# PWR.net
KiCad netlist of a schematic drawn in Altium Designer
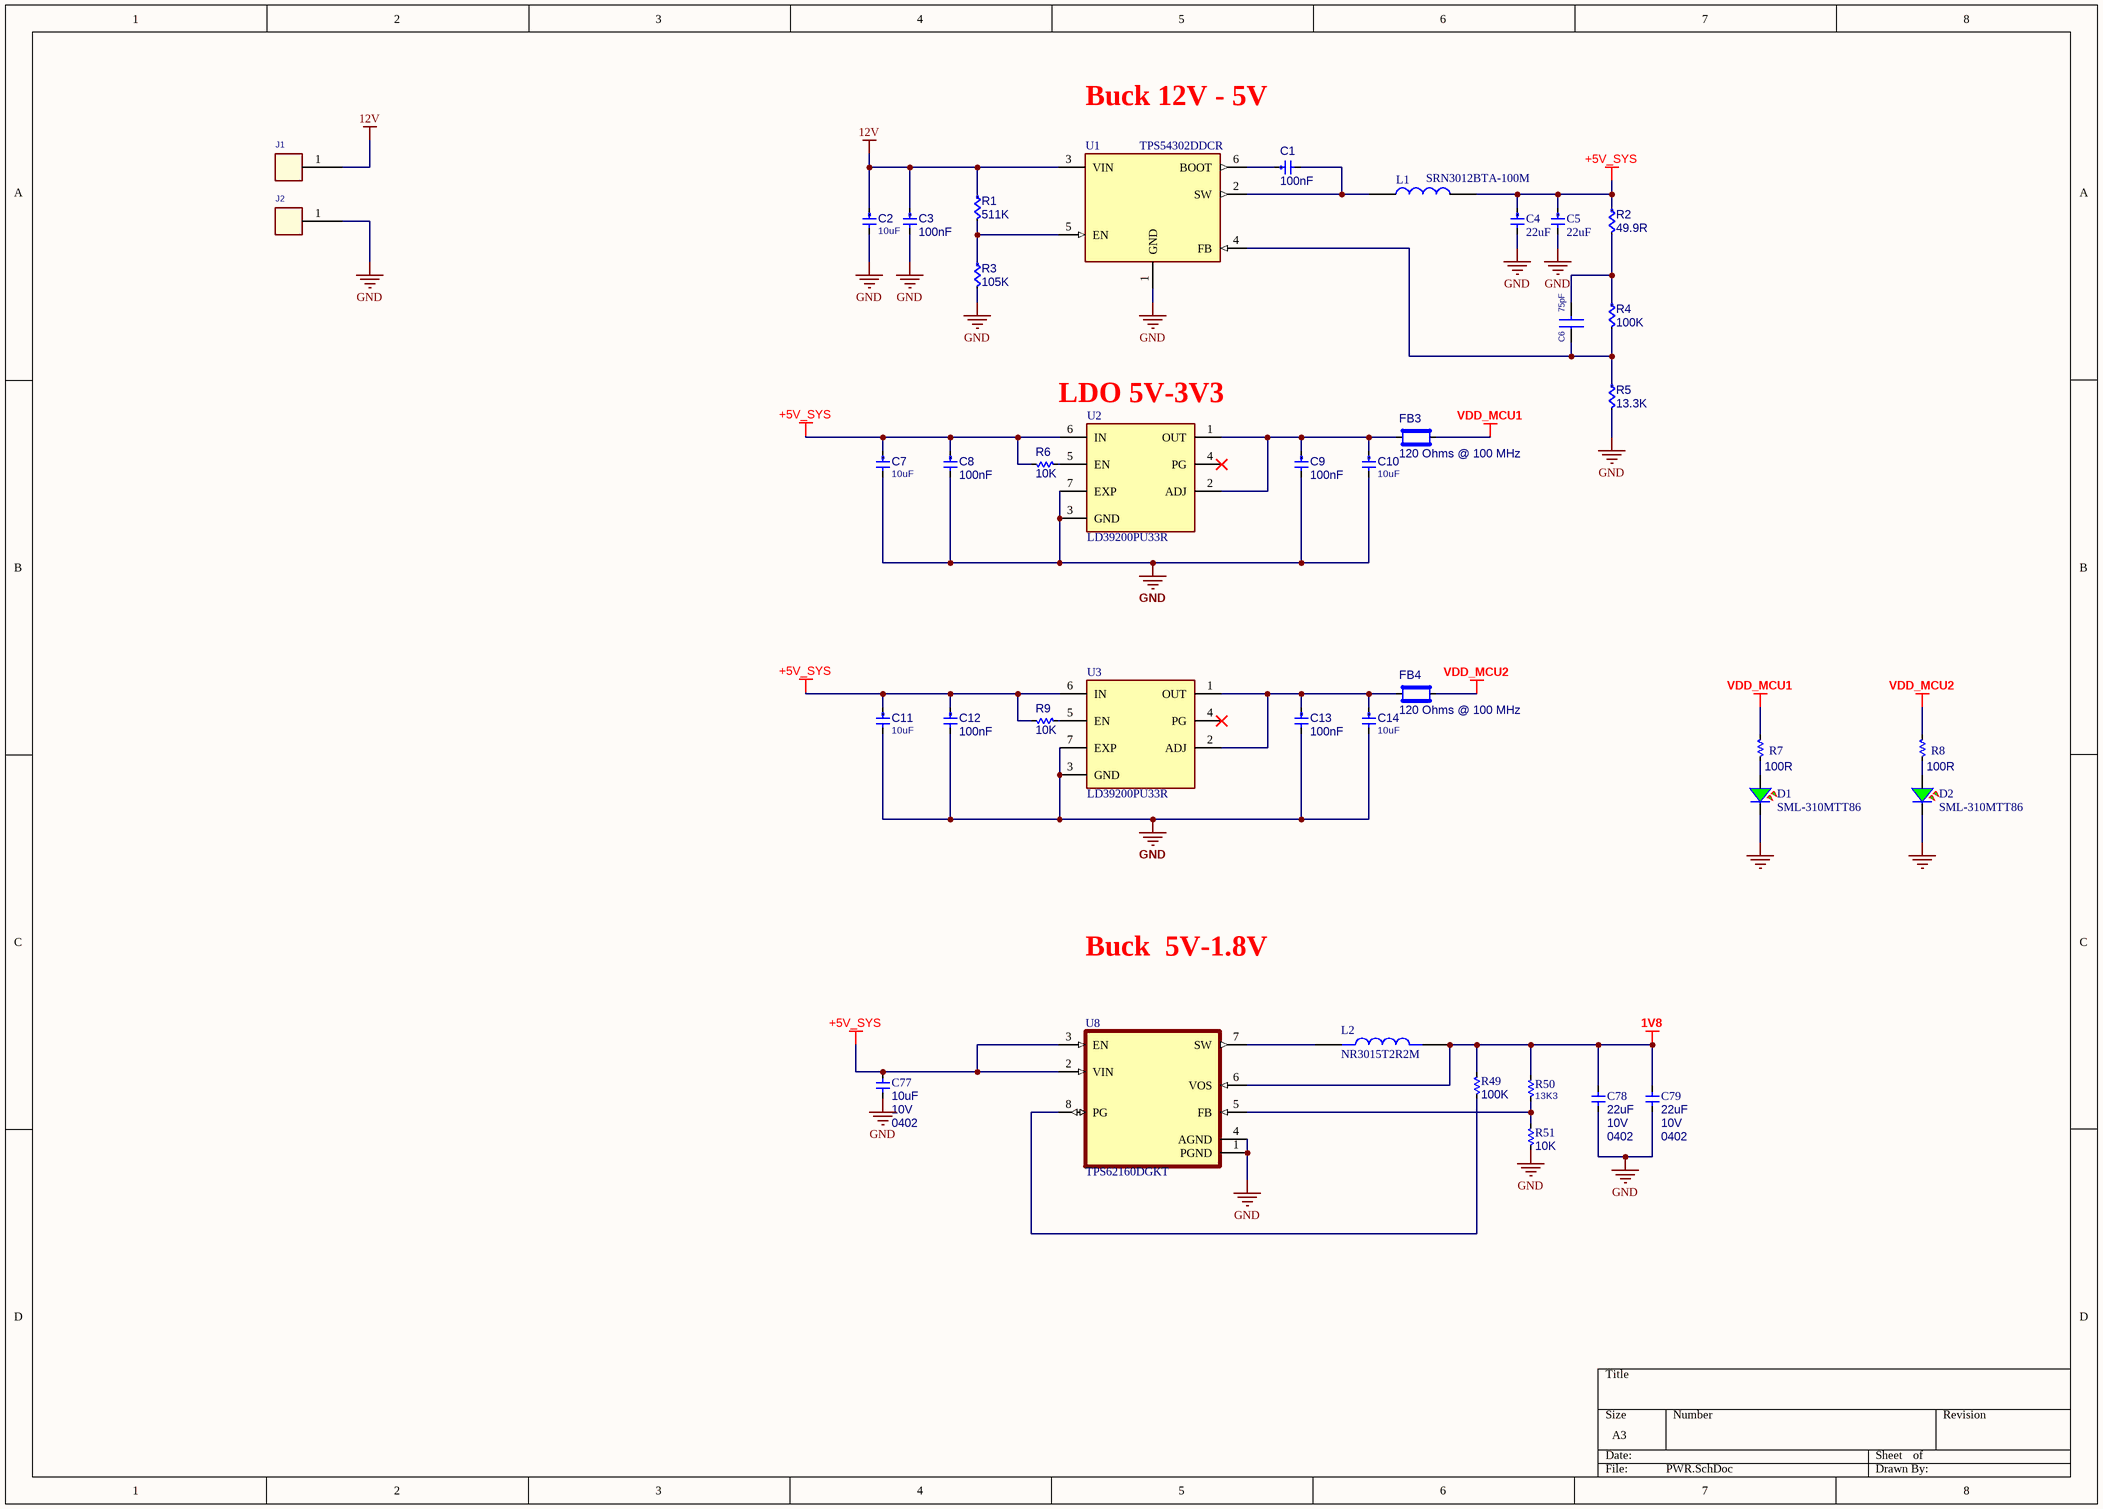
[diagram p0: PWR.SchDoc]

(export (version "E")
  (design (tool "Eeschema 10.0.6"))
  (components
    (comp (ref "C1")
      (value "CC0402KRX5R9BB104")
      (footprint "CAP0402")
      (description "CAP CER 0.1UF 50V X5R 0402")
      (fields
        (field (name "MANUFACTURER") "Yageo")
        (field (name "TOLERANCE") "10%")
        (field (name "CAPACITANCE") "100nF")
      )
      (libsource (lib "rtr") (part "CMP-00265-1"))
    )
    (comp (ref "C2")
      (value "GRM188R6YA106MA73D")
      (footprint "CAP0603-M")
      (description "CAP CER 10UF 35V X5R 0603")
      (fields
        (field (name "TOLERANCE") "20%")
        (field (name "VOLTAGE") "35V")
        (field (name "CAPACITANCE") "10uF")
      )
      (libsource (lib "rtr") (part "CMP-01031-1"))
    )
    (comp (ref "C3")
      (value "CC0402KRX5R9BB104")
      (footprint "CAP0402")
      (description "CAP CER 0.1UF 50V X5R 0402")
      (fields
        (field (name "MANUFACTURER") "Yageo")
        (field (name "TOLERANCE") "10%")
        (field (name "CAPACITANCE") "100nF")
      )
      (libsource (lib "rtr") (part "CMP-00265-1"))
    )
    (comp (ref "C4")
      (value "GRM158R61A226ME15D")
      (footprint "CAP0402")
      (description "CAP CER 22UF 10V X5R 0402")
      (fields
        (field (name "VOLTAGE") "10V")
        (field (name "TOLERANCE") "10%")
        (field (name "CAPACITANCE") "22uF")
      )
      (libsource (lib "CH961_CARRIER") (part "CMP-00520-1"))
    )
    (comp (ref "C5")
      (value "GRM158R61A226ME15D")
      (footprint "CAP0402")
      (description "CAP CER 22UF 10V X5R 0402")
      (fields
        (field (name "VOLTAGE") "10V")
        (field (name "TOLERANCE") "10%")
        (field (name "CAPACITANCE") "22uF")
      )
      (libsource (lib "CH961_CARRIER") (part "CMP-00520-1"))
    )
    (comp (ref "C6")
      (value "75pF")
      (footprint "CAP0402")
      (description "CAP CER 75PF 25V C0G/NP0 0402")
      (fields (field (name "MANUFACTURER") "YAGEO") (field (name "TOLERANCE") "5%"))
      (libsource (lib "motor MB1419") (part "CAP_Dup1_16"))
    )
    (comp (ref "C7")
      (value "GRM188R6YA106MA73D")
      (footprint "CAP0603")
      (description "CAP CER 10UF 35V X5R 0603")
      (fields
        (field (name "TOLERANCE") "20%")
        (field (name "VOLTAGE") "35V")
        (field (name "CAPACITANCE") "10uF")
      )
      (libsource (lib "rtr") (part "CMP-01031-1"))
    )
    (comp (ref "C8")
      (value "CC0402KRX5R9BB104")
      (footprint "CAP0402")
      (description "CAP CER 0.1UF 50V X5R 0402")
      (fields
        (field (name "MANUFACTURER") "Yageo")
        (field (name "TOLERANCE") "10%")
        (field (name "CAPACITANCE") "100nF")
      )
      (libsource (lib "rtr") (part "CMP-00265-1"))
    )
    (comp (ref "C9")
      (value "CC0402KRX5R9BB104")
      (footprint "CAP0402")
      (description "CAP CER 0.1UF 50V X5R 0402")
      (fields
        (field (name "MANUFACTURER") "Yageo")
        (field (name "TOLERANCE") "10%")
        (field (name "CAPACITANCE") "100nF")
      )
      (libsource (lib "rtr") (part "CMP-00265-1"))
    )
    (comp (ref "C10")
      (value "GRM188R6YA106MA73D")
      (footprint "CAP0603")
      (description "CAP CER 10UF 35V X5R 0603")
      (fields
        (field (name "TOLERANCE") "20%")
        (field (name "VOLTAGE") "35V")
        (field (name "CAPACITANCE") "10uF")
      )
      (libsource (lib "rtr") (part "CMP-01031-1"))
    )
    (comp (ref "C11")
      (value "GRM188R6YA106MA73D")
      (footprint "CAP0603")
      (description "CAP CER 10UF 35V X5R 0603")
      (fields
        (field (name "TOLERANCE") "20%")
        (field (name "VOLTAGE") "35V")
        (field (name "CAPACITANCE") "10uF")
      )
      (libsource (lib "rtr") (part "CMP-01031-1"))
    )
    (comp (ref "C12")
      (value "CC0402KRX5R9BB104")
      (footprint "CAP0402")
      (description "CAP CER 0.1UF 50V X5R 0402")
      (fields
        (field (name "MANUFACTURER") "Yageo")
        (field (name "TOLERANCE") "10%")
        (field (name "CAPACITANCE") "100nF")
      )
      (libsource (lib "rtr") (part "CMP-00265-1"))
    )
    (comp (ref "C13")
      (value "CC0402KRX5R9BB104")
      (footprint "CAP0402")
      (description "CAP CER 0.1UF 50V X5R 0402")
      (fields
        (field (name "MANUFACTURER") "Yageo")
        (field (name "TOLERANCE") "10%")
        (field (name "CAPACITANCE") "100nF")
      )
      (libsource (lib "rtr") (part "CMP-00265-1"))
    )
    (comp (ref "C14")
      (value "GRM188R6YA106MA73D")
      (footprint "CAP0603")
      (description "CAP CER 10UF 35V X5R 0603")
      (fields
        (field (name "TOLERANCE") "20%")
        (field (name "VOLTAGE") "35V")
        (field (name "CAPACITANCE") "10uF")
      )
      (libsource (lib "rtr") (part "CMP-01031-1"))
    )
    (comp (ref "C77")
      (value "10uF")
      (footprint "CAP0402")
      (description "Cap 10uF 10V 0402")
      (fields
        (field (name "MP") "GRT155R61A106ME13D")
        (field (name "VOLTAGE") "10V")
        (field (name "PACKAGE") "0402")
        (field (name "Comment") "CAP0402 10uF 10V")
      )
      (libsource (lib "RTR") (part "CAP0402 10uF 10V"))
    )
    (comp (ref "C78")
      (value "22uF")
      (footprint "CAP0402")
      (description "Cap 22uF 10V 0402")
      (fields
        (field (name "MP") "GRM158R61A226ME15D")
        (field (name "VOLTAGE") "10V")
        (field (name "PACKAGE") "0402")
        (field (name "Comment") "CAP0402 22uF 10V")
      )
      (libsource (lib "RTR") (part "CAP0402 22uF 10V"))
    )
    (comp (ref "C79")
      (value "22uF")
      (footprint "CAP0402")
      (description "Cap 22uF 10V 0402")
      (fields
        (field (name "MP") "GRM158R61A226ME15D")
        (field (name "VOLTAGE") "10V")
        (field (name "PACKAGE") "0402")
        (field (name "Comment") "CAP0402 22uF 10V")
      )
      (libsource (lib "RTR") (part "CAP0402 22uF 10V"))
    )
    (comp (ref "D1")
      (value "SML-310MTT86")
      (footprint "LED0603 GREEN")
      (description "LED GREEN CLEAR 0603 SMD")
      (libsource (lib "HeraJetson_Modified") (part "CMP-01130-2"))
    )
    (comp (ref "D2")
      (value "SML-310MTT86")
      (footprint "LED0603 GREEN")
      (description "LED GREEN CLEAR 0603 SMD")
      (libsource (lib "HeraJetson_Modified") (part "CMP-01130-2"))
    )
    (comp (ref "FB3")
      (value "BLM15PX121SZ1D")
      (footprint "FERRIT0402")
      (description "120 Ohms @ 100 MHz 1 Power Line Ferrite Bead 0402 (1005 Metric) 2A 55mOhm")
      (fields (field (name "IMPEDANCE @ FREQUENCY") "120 Ohms @ 100 MHz"))
      (libsource (lib "RTR") (part "BLM15PX121SZ1D"))
    )
    (comp (ref "FB4")
      (value "BLM15PX121SZ1D")
      (footprint "FERRIT0402")
      (description "120 Ohms @ 100 MHz 1 Power Line Ferrite Bead 0402 (1005 Metric) 2A 55mOhm")
      (fields (field (name "IMPEDANCE @ FREQUENCY") "120 Ohms @ 100 MHz"))
      (libsource (lib "RTR") (part "BLM15PX121SZ1D"))
    )
    (comp (ref "J1")
      (value "CON1")
      (footprint "wire1_220s")
      (description "SOLDER PADS")
      (libsource (lib "motor MB1419") (part "CON1"))
    )
    (comp (ref "J2")
      (value "CON1")
      (footprint "wire1_220s")
      (description "SOLDER PADS")
      (libsource (lib "motor MB1419") (part "CON1"))
    )
    (comp (ref "L1")
      (value "SRN3012BTA-100M")
      (footprint "SRN3012BTA-100M")
      (description "10uH")
      (libsource (lib "SRN3012BTA-330M") (part "SRN3012BTA-330M"))
    )
    (comp (ref "L2")
      (value "NR3015T2R2M")
      (footprint "IND_NR3015T2R2M")
      (description "2.2 ÂµH Shielded Drum Core, Wirewound Inductor 1.5 A 72mOhm Max Nonstandard")
      (fields (field (name "MF") "Taiyo Yuden"))
      (libsource (lib "RTR (1)") (part "NR3015T2R2M"))
    )
    (comp (ref "R1")
      (value "511K")
      (footprint "RES0402")
      (description "RES SMD 511K OHM 1% 1/16W 0402")
      (fields (field (name "MANUFACTURER") "Yageo") (field (name "TOLERANCE") "1%"))
      (libsource (lib "rtr") (part "CMP-00299-1_1"))
    )
    (comp (ref "R2")
      (value "49.9R")
      (footprint "RES0402")
      (description "RES SMD 49.9R OHM 1% 1/16W 0402")
      (fields (field (name "MANUFACTURER") "Yageo") (field (name "TOLERANCE") "1%"))
      (libsource (lib "rtr") (part "CMP-00299-1_1"))
    )
    (comp (ref "R3")
      (value "105K")
      (footprint "RES0402")
      (description "RES SMD 105K OHM 1% 1/16W 0402")
      (fields (field (name "MANUFACTURER") "Yageo") (field (name "TOLERANCE") "1%"))
      (libsource (lib "rtr") (part "CMP-00299-1_1"))
    )
    (comp (ref "R4")
      (value "100K")
      (footprint "RES0402")
      (description "RES SMD 100K OHM 1% 1/16W 0402")
      (fields (field (name "MANUFACTURER") "Yageo") (field (name "TOLERANCE") "1%"))
      (libsource (lib "rtr") (part "CMP-00299-1_1"))
    )
    (comp (ref "R5")
      (value "13.3K")
      (footprint "RES0402")
      (description "RES SMD 13.3K OHM 1% 1/16W 0402")
      (fields (field (name "MANUFACTURER") "Yageo") (field (name "TOLERANCE") "1%"))
      (libsource (lib "rtr") (part "CMP-00299-1_1"))
    )
    (comp (ref "R6")
      (value "10K")
      (footprint "RES0402")
      (description "RES 10K 0402")
      (fields (field (name "MP") "RC0402FR-0710KL") (field (name "Comment") "RES0402 10K"))
      (libsource (lib "RTR") (part "RES0402 10K"))
    )
    (comp (ref "R7")
      (value "100R")
      (footprint "RES0402")
      (description "RES 100R 0402")
      (fields (field (name "MP") "RC0402FR-07100RL") (field (name "Comment") "RES0402 100R"))
      (libsource (lib "RTR") (part "RES0402 100R"))
    )
    (comp (ref "R8")
      (value "100R")
      (footprint "RES0402")
      (description "RES 100R 0402")
      (fields (field (name "MP") "RC0402FR-07100RL") (field (name "Comment") "RES0402 100R"))
      (libsource (lib "RTR") (part "RES0402 100R"))
    )
    (comp (ref "R9")
      (value "10K")
      (footprint "RES0402")
      (description "RES 10K 0402")
      (fields (field (name "MP") "RC0402FR-0710KL") (field (name "Comment") "RES0402 10K"))
      (libsource (lib "RTR") (part "RES0402 10K"))
    )
    (comp (ref "R49")
      (value "100K")
      (footprint "RES0402")
      (description "RES 100K 0402")
      (fields (field (name "MP") "RC0402FR-07100KL") (field (name "Comment") "RES0402 100K"))
      (libsource (lib "RTR") (part "RES0402 100K"))
    )
    (comp (ref "R50")
      (value "13K3")
      (footprint "RES0402")
      (description "RES 13K3 0402")
      (fields (field (name "MP") "RC0402FR-0713K3L") (field (name "Comment") "RES0402 13K3"))
      (libsource (lib "RTR") (part "RES0402 13K3"))
    )
    (comp (ref "R51")
      (value "10K")
      (footprint "RES0402")
      (description "RES 10K 0402")
      (fields (field (name "MP") "RC0402FR-0710KL") (field (name "Comment") "RES0402 10K"))
      (libsource (lib "RTR") (part "RES0402 10K"))
    )
    (comp (ref "U1")
      (value "TPS54302DDCR")
      (footprint "SOT95P280X110-6N - duplicate1")
      (description "4.5-V to 28-V Input, 3-A Output, EMI Friendly Synchronous Step-Down Converter")
      (fields (field (name "MF") "Texas Instruments"))
      (libsource (lib "TPS54302DDCR") (part "TPS54302DDCR"))
    )
    (comp (ref "U2")
      (value "LD39200PU33R")
      (footprint "LD39200PUR")
      (description "LDO IC 1 Output 2A 6-DFN _3x3_")
      (fields (field (name "MF") "STMicroelectronics"))
      (libsource (lib "RTR") (part "LD39200PUR"))
    )
    (comp (ref "U3")
      (value "LD39200PU33R")
      (footprint "LD39200PUR")
      (description "LDO IC 1 Output 2A 6-DFN _3x3_")
      (fields (field (name "MF") "STMicroelectronics"))
      (libsource (lib "RTR") (part "LD39200PUR"))
    )
    (comp (ref "U8")
      (value "TPS62160DGKT")
      (footprint "SOP65P490X110-8N")
      (description "3V-17V 1A Step-Down Converters with DCS-Controlâ„¢")
      (fields (field (name "MF") "Texas Instruments"))
      (libsource (lib "RTR (1)") (part "TPS62160DGKT"))
    )
  )
  (nets
    (net (code "1") (name "+5V_SYS") (class "Default")
      (node (ref "C11") (pin "1") (pinfunction "1_1") (pintype "passive"))
      (node (ref "C12") (pin "1") (pinfunction "1_1") (pintype "passive"))
      (node (ref "C4") (pin "1") (pinfunction "1_1") (pintype "passive"))
      (node (ref "C5") (pin "1") (pinfunction "1_1") (pintype "passive"))
      (node (ref "C7") (pin "1") (pinfunction "1_1") (pintype "passive"))
      (node (ref "C77") (pin "2") (pinfunction "2_2") (pintype "passive"))
      (node (ref "C8") (pin "1") (pinfunction "1_1") (pintype "passive"))
      (node (ref "L1") (pin "2") (pinfunction "2_2") (pintype "passive"))
      (node (ref "R2") (pin "1") (pinfunction "1_1") (pintype "passive"))
      (node (ref "R6") (pin "2") (pinfunction "2_2") (pintype "passive"))
      (node (ref "R9") (pin "2") (pinfunction "2_2") (pintype "passive"))
      (node (ref "U2") (pin "6") (pinfunction "IN_6") (pintype "passive"))
      (node (ref "U3") (pin "6") (pinfunction "IN_6") (pintype "passive"))
      (node (ref "U8") (pin "2") (pinfunction "VIN_2") (pintype "input"))
      (node (ref "U8") (pin "3") (pinfunction "EN_3") (pintype "input"))
    )
    (net (code "2") (name "1V8") (class "Default")
      (node (ref "C78") (pin "2") (pinfunction "2_2") (pintype "passive"))
      (node (ref "C79") (pin "2") (pinfunction "2_2") (pintype "passive"))
      (node (ref "L2") (pin "2") (pinfunction "2_2") (pintype "passive"))
      (node (ref "R49") (pin "2") (pinfunction "2_2") (pintype "passive"))
      (node (ref "R50") (pin "2") (pinfunction "2_2") (pintype "passive"))
      (node (ref "U8") (pin "6") (pinfunction "VOS_6") (pintype "input"))
    )
    (net (code "3") (name "12V") (class "Default")
      (node (ref "C2") (pin "1") (pinfunction "1_1") (pintype "passive"))
      (node (ref "C3") (pin "1") (pinfunction "1_1") (pintype "passive"))
      (node (ref "J1") (pin "1") (pinfunction "1_1") (pintype "passive"))
      (node (ref "R1") (pin "1") (pinfunction "1_1") (pintype "passive"))
      (node (ref "U1") (pin "3") (pinfunction "VIN_3") (pintype "power_in"))
    )
    (net (code "4") (name "GND") (class "Default")
      (node (ref "C10") (pin "2") (pinfunction "2_2") (pintype "passive"))
      (node (ref "C11") (pin "2") (pinfunction "2_2") (pintype "passive"))
      (node (ref "C12") (pin "2") (pinfunction "2_2") (pintype "passive"))
      (node (ref "C13") (pin "2") (pinfunction "2_2") (pintype "passive"))
      (node (ref "C14") (pin "2") (pinfunction "2_2") (pintype "passive"))
      (node (ref "C2") (pin "2") (pinfunction "2_2") (pintype "passive"))
      (node (ref "C3") (pin "2") (pinfunction "2_2") (pintype "passive"))
      (node (ref "C4") (pin "2") (pinfunction "2_2") (pintype "passive"))
      (node (ref "C5") (pin "2") (pinfunction "2_2") (pintype "passive"))
      (node (ref "C7") (pin "2") (pinfunction "2_2") (pintype "passive"))
      (node (ref "C77") (pin "1") (pinfunction "1_1") (pintype "passive"))
      (node (ref "C78") (pin "1") (pinfunction "1_1") (pintype "passive"))
      (node (ref "C79") (pin "1") (pinfunction "1_1") (pintype "passive"))
      (node (ref "C8") (pin "2") (pinfunction "2_2") (pintype "passive"))
      (node (ref "C9") (pin "2") (pinfunction "2_2") (pintype "passive"))
      (node (ref "D1") (pin "1") (pinfunction "1_1") (pintype "passive"))
      (node (ref "D2") (pin "1") (pinfunction "1_1") (pintype "passive"))
      (node (ref "J2") (pin "1") (pinfunction "1_1") (pintype "passive"))
      (node (ref "R3") (pin "2") (pinfunction "2_2") (pintype "passive"))
      (node (ref "R5") (pin "2") (pinfunction "2_2") (pintype "passive"))
      (node (ref "R51") (pin "1") (pinfunction "1_1") (pintype "passive"))
      (node (ref "U1") (pin "1") (pinfunction "GND_1") (pintype "power_in"))
      (node (ref "U2") (pin "3") (pinfunction "GND_3") (pintype "passive"))
      (node (ref "U2") (pin "7") (pinfunction "EXP_7") (pintype "passive"))
      (node (ref "U3") (pin "3") (pinfunction "GND_3") (pintype "passive"))
      (node (ref "U3") (pin "7") (pinfunction "EXP_7") (pintype "passive"))
      (node (ref "U8") (pin "1") (pinfunction "PGND_1") (pintype "power_in"))
      (node (ref "U8") (pin "4") (pinfunction "AGND_4") (pintype "power_in"))
    )
    (net (code "5") (name "Net-(C6-Pad2)") (class "Default")
      (node (ref "C6") (pin "2") (pinfunction "2_2") (pintype "passive"))
      (node (ref "R2") (pin "2") (pinfunction "2_2") (pintype "passive"))
      (node (ref "R4") (pin "1") (pinfunction "1_1") (pintype "passive"))
    )
    (net (code "6") (name "Net-(D1-Pad2)") (class "Default")
      (node (ref "D1") (pin "2") (pinfunction "2_2") (pintype "passive"))
      (node (ref "R7") (pin "1") (pinfunction "1_1") (pintype "passive"))
    )
    (net (code "7") (name "Net-(D2-Pad2)") (class "Default")
      (node (ref "D2") (pin "2") (pinfunction "2_2") (pintype "passive"))
      (node (ref "R8") (pin "1") (pinfunction "1_1") (pintype "passive"))
    )
    (net (code "8") (name "Net-(U1-BOOT)") (class "Default")
      (node (ref "C1") (pin "1") (pinfunction "1_1") (pintype "passive"))
      (node (ref "U1") (pin "6") (pinfunction "BOOT_6") (pintype "output"))
    )
    (net (code "9") (name "Net-(U1-EN)") (class "Default")
      (node (ref "R1") (pin "2") (pinfunction "2_2") (pintype "passive"))
      (node (ref "R3") (pin "1") (pinfunction "1_1") (pintype "passive"))
      (node (ref "U1") (pin "5") (pinfunction "EN_5") (pintype "input"))
    )
    (net (code "10") (name "Net-(U1-FB)") (class "Default")
      (node (ref "C6") (pin "1") (pinfunction "1_1") (pintype "passive"))
      (node (ref "R4") (pin "2") (pinfunction "2_2") (pintype "passive"))
      (node (ref "R5") (pin "1") (pinfunction "1_1") (pintype "passive"))
      (node (ref "U1") (pin "4") (pinfunction "FB_4") (pintype "input"))
    )
    (net (code "11") (name "Net-(U1-SW)") (class "Default")
      (node (ref "C1") (pin "2") (pinfunction "2_2") (pintype "passive"))
      (node (ref "L1") (pin "1") (pinfunction "1_1") (pintype "passive"))
      (node (ref "U1") (pin "2") (pinfunction "SW_2") (pintype "output"))
    )
    (net (code "12") (name "Net-(U2-ADJ)") (class "Default")
      (node (ref "C10") (pin "1") (pinfunction "1_1") (pintype "passive"))
      (node (ref "C9") (pin "1") (pinfunction "1_1") (pintype "passive"))
      (node (ref "FB3") (pin "1") (pinfunction "1_1") (pintype "passive"))
      (node (ref "U2") (pin "1") (pinfunction "OUT_1") (pintype "passive"))
      (node (ref "U2") (pin "2") (pinfunction "ADJ_2") (pintype "passive"))
    )
    (net (code "13") (name "Net-(U2-EN)") (class "Default")
      (node (ref "R6") (pin "1") (pinfunction "1_1") (pintype "passive"))
      (node (ref "U2") (pin "5") (pinfunction "EN_5") (pintype "passive"))
    )
    (net (code "14") (name "Net-(U3-ADJ)") (class "Default")
      (node (ref "C13") (pin "1") (pinfunction "1_1") (pintype "passive"))
      (node (ref "C14") (pin "1") (pinfunction "1_1") (pintype "passive"))
      (node (ref "FB4") (pin "1") (pinfunction "1_1") (pintype "passive"))
      (node (ref "U3") (pin "1") (pinfunction "OUT_1") (pintype "passive"))
      (node (ref "U3") (pin "2") (pinfunction "ADJ_2") (pintype "passive"))
    )
    (net (code "15") (name "Net-(U3-EN)") (class "Default")
      (node (ref "R9") (pin "1") (pinfunction "1_1") (pintype "passive"))
      (node (ref "U3") (pin "5") (pinfunction "EN_5") (pintype "passive"))
    )
    (net (code "16") (name "Net-(U8-FB)") (class "Default")
      (node (ref "R50") (pin "1") (pinfunction "1_1") (pintype "passive"))
      (node (ref "R51") (pin "2") (pinfunction "2_2") (pintype "passive"))
      (node (ref "U8") (pin "5") (pinfunction "FB_5") (pintype "input"))
    )
    (net (code "17") (name "Net-(U8-PG)") (class "Default")
      (node (ref "R49") (pin "1") (pinfunction "1_1") (pintype "passive"))
      (node (ref "U8") (pin "8") (pinfunction "PG_8") (pintype "bidirectional"))
    )
    (net (code "18") (name "Net-(U8-SW)") (class "Default")
      (node (ref "L2") (pin "1") (pinfunction "1_1") (pintype "passive"))
      (node (ref "U8") (pin "7") (pinfunction "SW_7") (pintype "output"))
    )
    (net (code "19") (name "VDD_MCU1") (class "Default")
      (node (ref "FB3") (pin "2") (pinfunction "2_2") (pintype "passive"))
      (node (ref "R7") (pin "2") (pinfunction "2_2") (pintype "passive"))
    )
    (net (code "20") (name "VDD_MCU2") (class "Default")
      (node (ref "FB4") (pin "2") (pinfunction "2_2") (pintype "passive"))
      (node (ref "R8") (pin "2") (pinfunction "2_2") (pintype "passive"))
    )
    (net (code "21") (name "unconnected-(U2-PG-Pad4)") (class "Default")
      (node (ref "U2") (pin "4") (pinfunction "PG_4") (pintype "passive+no_connect"))
    )
    (net (code "22") (name "unconnected-(U3-PG-Pad4)") (class "Default")
      (node (ref "U3") (pin "4") (pinfunction "PG_4") (pintype "passive+no_connect"))
    )
  )
)
